# schema.net
KiCad netlist of a schematic drawn in EAGLE
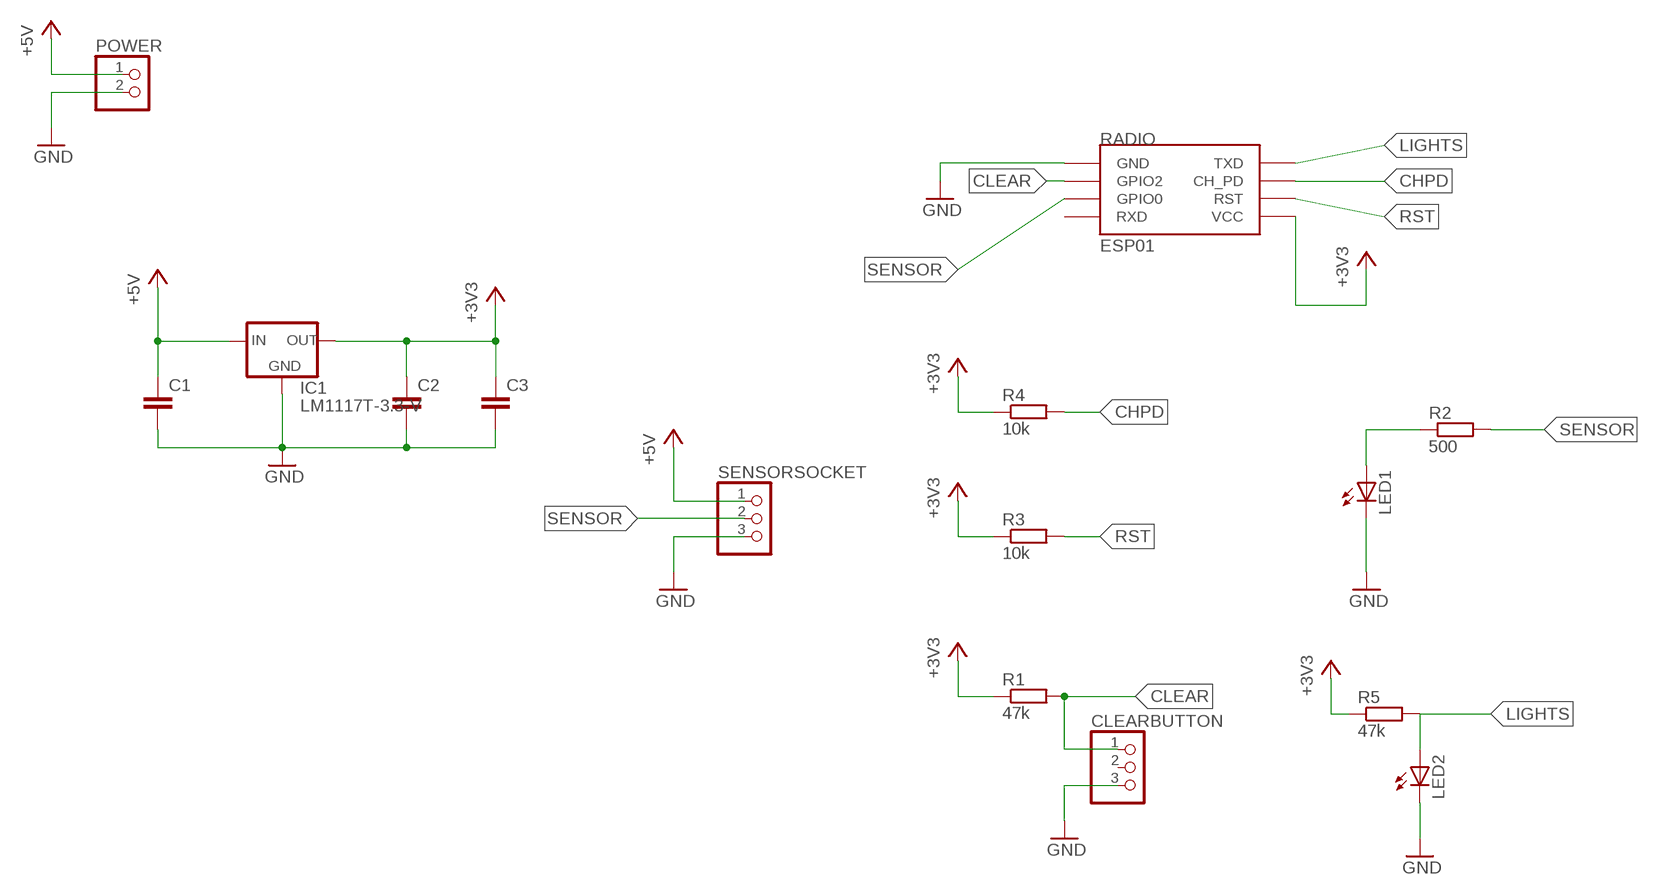
[diagram p0: schematic, sheet 1]

(export (version "E")
  (design (tool "Eeschema 10.0.6"))
  (components
    (comp (ref "C1")
      (value "C-EU025-024X044")
      (footprint "eagle-import:C025-024X044")
      (libsource (lib "eagle-import") (part "C-EU025-024X044"))
    )
    (comp (ref "C2")
      (value "C-EU025-024X044")
      (footprint "eagle-import:C025-024X044")
      (libsource (lib "eagle-import") (part "C-EU025-024X044"))
    )
    (comp (ref "C3")
      (value "C-EU025-024X044")
      (footprint "eagle-import:C025-024X044")
      (libsource (lib "eagle-import") (part "C-EU025-024X044"))
    )
    (comp (ref "CLEARBUTTON")
      (value "PINHD-1X3")
      (footprint "eagle-import:1X03")
      (libsource (lib "eagle-import") (part "PINHD-1X3"))
    )
    (comp (ref "IC1")
      (value "LM1117T-3.3-V")
      (footprint "eagle-import:TO220V")
      (libsource (lib "eagle-import") (part "LM1117T--V3.3"))
    )
    (comp (ref "LED1")
      (value "LED3MM")
      (footprint "eagle-import:LED3MM")
      (libsource (lib "eagle-import") (part "LED3MM"))
    )
    (comp (ref "LED2")
      (value "LED3MM")
      (footprint "eagle-import:LED3MM")
      (libsource (lib "eagle-import") (part "LED3MM"))
    )
    (comp (ref "POWER")
      (value "PINHD-1X2")
      (footprint "eagle-import:1X02")
      (libsource (lib "eagle-import") (part "PINHD-1X2"))
    )
    (comp (ref "R1")
      (value "47k")
      (footprint "eagle-import:0204_5")
      (libsource (lib "eagle-import") (part "R-EU_0204/5"))
    )
    (comp (ref "R2")
      (value "500")
      (footprint "eagle-import:0204_5")
      (libsource (lib "eagle-import") (part "R-EU_0204/5"))
    )
    (comp (ref "R3")
      (value "10k")
      (footprint "eagle-import:0204_5")
      (libsource (lib "eagle-import") (part "R-EU_0204/5"))
    )
    (comp (ref "R4")
      (value "10k")
      (footprint "eagle-import:0204_5")
      (libsource (lib "eagle-import") (part "R-EU_0204/5"))
    )
    (comp (ref "R5")
      (value "47k")
      (footprint "eagle-import:0204_5")
      (libsource (lib "eagle-import") (part "R-EU_0204/5"))
    )
    (comp (ref "RADIO")
      (value "ESP01")
      (footprint "eagle-import:ESP01")
      (libsource (lib "eagle-import") (part "ESP01"))
    )
    (comp (ref "SENSORSOCKET")
      (value "PINHD-1X3")
      (footprint "eagle-import:1X03")
      (libsource (lib "eagle-import") (part "PINHD-1X3"))
    )
  )
  (nets
    (net (code "1") (name "+3V3") (class "Default")
      (node (ref "C2") (pin "1") (pinfunction "1_1") (pintype "passive"))
      (node (ref "C3") (pin "1") (pinfunction "1_1") (pintype "passive"))
      (node (ref "IC1") (pin "2") (pinfunction "OUT_2") (pintype "passive"))
      (node (ref "R1") (pin "1") (pinfunction "1_1") (pintype "passive"))
      (node (ref "R3") (pin "1") (pinfunction "1_1") (pintype "passive"))
      (node (ref "R4") (pin "1") (pinfunction "1_1") (pintype "passive"))
      (node (ref "R5") (pin "1") (pinfunction "1_1") (pintype "passive"))
      (node (ref "RADIO") (pin "VCC") (pinfunction "VCC_VCC") (pintype "bidirectional"))
    )
    (net (code "2") (name "+5V") (class "Default")
      (node (ref "C1") (pin "1") (pinfunction "1_1") (pintype "passive"))
      (node (ref "IC1") (pin "3") (pinfunction "IN_3") (pintype "input"))
      (node (ref "POWER") (pin "1") (pinfunction "1_1") (pintype "passive"))
      (node (ref "SENSORSOCKET") (pin "1") (pinfunction "1_1") (pintype "passive"))
    )
    (net (code "3") (name "CHPD") (class "Default")
      (node (ref "R4") (pin "2") (pinfunction "2_2") (pintype "passive"))
      (node (ref "RADIO") (pin "CH_PD") (pinfunction "CH_PD_CH_PD") (pintype "bidirectional"))
    )
    (net (code "4") (name "CLEAR") (class "Default")
      (node (ref "CLEARBUTTON") (pin "1") (pinfunction "1_1") (pintype "passive"))
      (node (ref "R1") (pin "2") (pinfunction "2_2") (pintype "passive"))
      (node (ref "RADIO") (pin "GPIO2") (pinfunction "GPIO2_GPIO2") (pintype "bidirectional"))
    )
    (net (code "5") (name "GND") (class "Default")
      (node (ref "C1") (pin "2") (pinfunction "2_2") (pintype "passive"))
      (node (ref "C2") (pin "2") (pinfunction "2_2") (pintype "passive"))
      (node (ref "C3") (pin "2") (pinfunction "2_2") (pintype "passive"))
      (node (ref "CLEARBUTTON") (pin "3") (pinfunction "3_3") (pintype "passive"))
      (node (ref "IC1") (pin "1") (pinfunction "GND_1") (pintype "input"))
      (node (ref "LED1") (pin "K") (pinfunction "C_K") (pintype "passive"))
      (node (ref "LED2") (pin "K") (pinfunction "C_K") (pintype "passive"))
      (node (ref "POWER") (pin "2") (pinfunction "2_2") (pintype "passive"))
      (node (ref "RADIO") (pin "GND") (pinfunction "GND_GND") (pintype "bidirectional"))
      (node (ref "SENSORSOCKET") (pin "3") (pinfunction "3_3") (pintype "passive"))
    )
    (net (code "6") (name "LIGHTS") (class "Default")
      (node (ref "LED2") (pin "A") (pinfunction "A_A") (pintype "passive"))
      (node (ref "R5") (pin "2") (pinfunction "2_2") (pintype "passive"))
      (node (ref "RADIO") (pin "TX") (pinfunction "TXD_TX") (pintype "bidirectional"))
    )
    (net (code "7") (name "Net-(LED1-PadA)") (class "Default")
      (node (ref "LED1") (pin "A") (pinfunction "A_A") (pintype "passive"))
      (node (ref "R2") (pin "1") (pinfunction "1_1") (pintype "passive"))
    )
    (net (code "8") (name "RST") (class "Default")
      (node (ref "R3") (pin "2") (pinfunction "2_2") (pintype "passive"))
      (node (ref "RADIO") (pin "RST") (pinfunction "RST_RST") (pintype "bidirectional"))
    )
    (net (code "9") (name "SENSOR") (class "Default")
      (node (ref "R2") (pin "2") (pinfunction "2_2") (pintype "passive"))
      (node (ref "RADIO") (pin "GPIO0") (pinfunction "GPIO0_GPIO0") (pintype "bidirectional"))
      (node (ref "SENSORSOCKET") (pin "2") (pinfunction "2_2") (pintype "passive"))
    )
    (net (code "10") (name "unconnected-(CLEARBUTTON-Pad2)") (class "Default")
      (node (ref "CLEARBUTTON") (pin "2") (pinfunction "2_2") (pintype "passive"))
    )
    (net (code "11") (name "unconnected-(RADIO-RXD-PadRX)") (class "Default")
      (node (ref "RADIO") (pin "RX") (pinfunction "RXD_RX") (pintype "bidirectional"))
    )
  )
)
